# zcpn.net
KiCad netlist of a schematic drawn in EAGLE
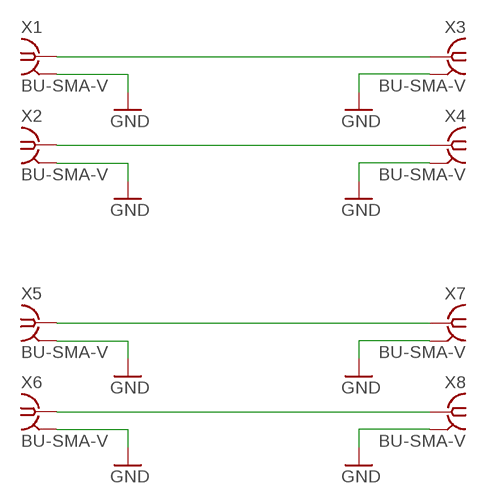
[diagram p0: schematic, sheet 1]

(export (version "E")
  (design (tool "Eeschema 10.0.6"))
  (components
    (comp (ref "X1")
      (value "BU-SMA-V")
      (footprint "eagle-import:BU-SMA-V")
      (libsource (lib "eagle-import") (part "BU-SMA-V"))
    )
    (comp (ref "X2")
      (value "BU-SMA-V")
      (footprint "eagle-import:BU-SMA-V")
      (libsource (lib "eagle-import") (part "BU-SMA-V"))
    )
    (comp (ref "X3")
      (value "BU-SMA-V")
      (footprint "eagle-import:BU-SMA-V")
      (libsource (lib "eagle-import") (part "BU-SMA-V"))
    )
    (comp (ref "X4")
      (value "BU-SMA-V")
      (footprint "eagle-import:BU-SMA-V")
      (libsource (lib "eagle-import") (part "BU-SMA-V"))
    )
    (comp (ref "X5")
      (value "BU-SMA-V")
      (footprint "eagle-import:BU-SMA-V")
      (libsource (lib "eagle-import") (part "BU-SMA-V"))
    )
    (comp (ref "X6")
      (value "BU-SMA-V")
      (footprint "eagle-import:BU-SMA-V")
      (libsource (lib "eagle-import") (part "BU-SMA-V"))
    )
    (comp (ref "X7")
      (value "BU-SMA-V")
      (footprint "eagle-import:BU-SMA-V")
      (libsource (lib "eagle-import") (part "BU-SMA-V"))
    )
    (comp (ref "X8")
      (value "BU-SMA-V")
      (footprint "eagle-import:BU-SMA-V")
      (libsource (lib "eagle-import") (part "BU-SMA-V"))
    )
  )
  (nets
    (net (code "1") (name "GND") (class "Default")
      (node (ref "X1") (pin "2") (pinfunction "2_2") (pintype "passive"))
      (node (ref "X1") (pin "3") (pinfunction "2_3") (pintype "passive"))
      (node (ref "X1") (pin "4") (pinfunction "2_4") (pintype "passive"))
      (node (ref "X1") (pin "5") (pinfunction "2_5") (pintype "passive"))
      (node (ref "X2") (pin "2") (pinfunction "2_2") (pintype "passive"))
      (node (ref "X2") (pin "3") (pinfunction "2_3") (pintype "passive"))
      (node (ref "X2") (pin "4") (pinfunction "2_4") (pintype "passive"))
      (node (ref "X2") (pin "5") (pinfunction "2_5") (pintype "passive"))
      (node (ref "X3") (pin "2") (pinfunction "2_2") (pintype "passive"))
      (node (ref "X3") (pin "3") (pinfunction "2_3") (pintype "passive"))
      (node (ref "X3") (pin "4") (pinfunction "2_4") (pintype "passive"))
      (node (ref "X3") (pin "5") (pinfunction "2_5") (pintype "passive"))
      (node (ref "X4") (pin "2") (pinfunction "2_2") (pintype "passive"))
      (node (ref "X4") (pin "3") (pinfunction "2_3") (pintype "passive"))
      (node (ref "X4") (pin "4") (pinfunction "2_4") (pintype "passive"))
      (node (ref "X4") (pin "5") (pinfunction "2_5") (pintype "passive"))
      (node (ref "X5") (pin "2") (pinfunction "2_2") (pintype "passive"))
      (node (ref "X5") (pin "3") (pinfunction "2_3") (pintype "passive"))
      (node (ref "X5") (pin "4") (pinfunction "2_4") (pintype "passive"))
      (node (ref "X5") (pin "5") (pinfunction "2_5") (pintype "passive"))
      (node (ref "X6") (pin "2") (pinfunction "2_2") (pintype "passive"))
      (node (ref "X6") (pin "3") (pinfunction "2_3") (pintype "passive"))
      (node (ref "X6") (pin "4") (pinfunction "2_4") (pintype "passive"))
      (node (ref "X6") (pin "5") (pinfunction "2_5") (pintype "passive"))
      (node (ref "X7") (pin "2") (pinfunction "2_2") (pintype "passive"))
      (node (ref "X7") (pin "3") (pinfunction "2_3") (pintype "passive"))
      (node (ref "X7") (pin "4") (pinfunction "2_4") (pintype "passive"))
      (node (ref "X7") (pin "5") (pinfunction "2_5") (pintype "passive"))
      (node (ref "X8") (pin "2") (pinfunction "2_2") (pintype "passive"))
      (node (ref "X8") (pin "3") (pinfunction "2_3") (pintype "passive"))
      (node (ref "X8") (pin "4") (pinfunction "2_4") (pintype "passive"))
      (node (ref "X8") (pin "5") (pinfunction "2_5") (pintype "passive"))
    )
    (net (code "2") (name "Net-(X1-Pad1)") (class "Default")
      (node (ref "X1") (pin "1") (pinfunction "1_1") (pintype "passive"))
      (node (ref "X3") (pin "1") (pinfunction "1_1") (pintype "passive"))
    )
    (net (code "3") (name "Net-(X2-Pad1)") (class "Default")
      (node (ref "X2") (pin "1") (pinfunction "1_1") (pintype "passive"))
      (node (ref "X4") (pin "1") (pinfunction "1_1") (pintype "passive"))
    )
    (net (code "4") (name "Net-(X5-Pad1)") (class "Default")
      (node (ref "X5") (pin "1") (pinfunction "1_1") (pintype "passive"))
      (node (ref "X7") (pin "1") (pinfunction "1_1") (pintype "passive"))
    )
    (net (code "5") (name "Net-(X6-Pad1)") (class "Default")
      (node (ref "X6") (pin "1") (pinfunction "1_1") (pintype "passive"))
      (node (ref "X8") (pin "1") (pinfunction "1_1") (pintype "passive"))
    )
  )
)
